# fyp_board_rev3.net
KiCad netlist of a schematic drawn in EAGLE
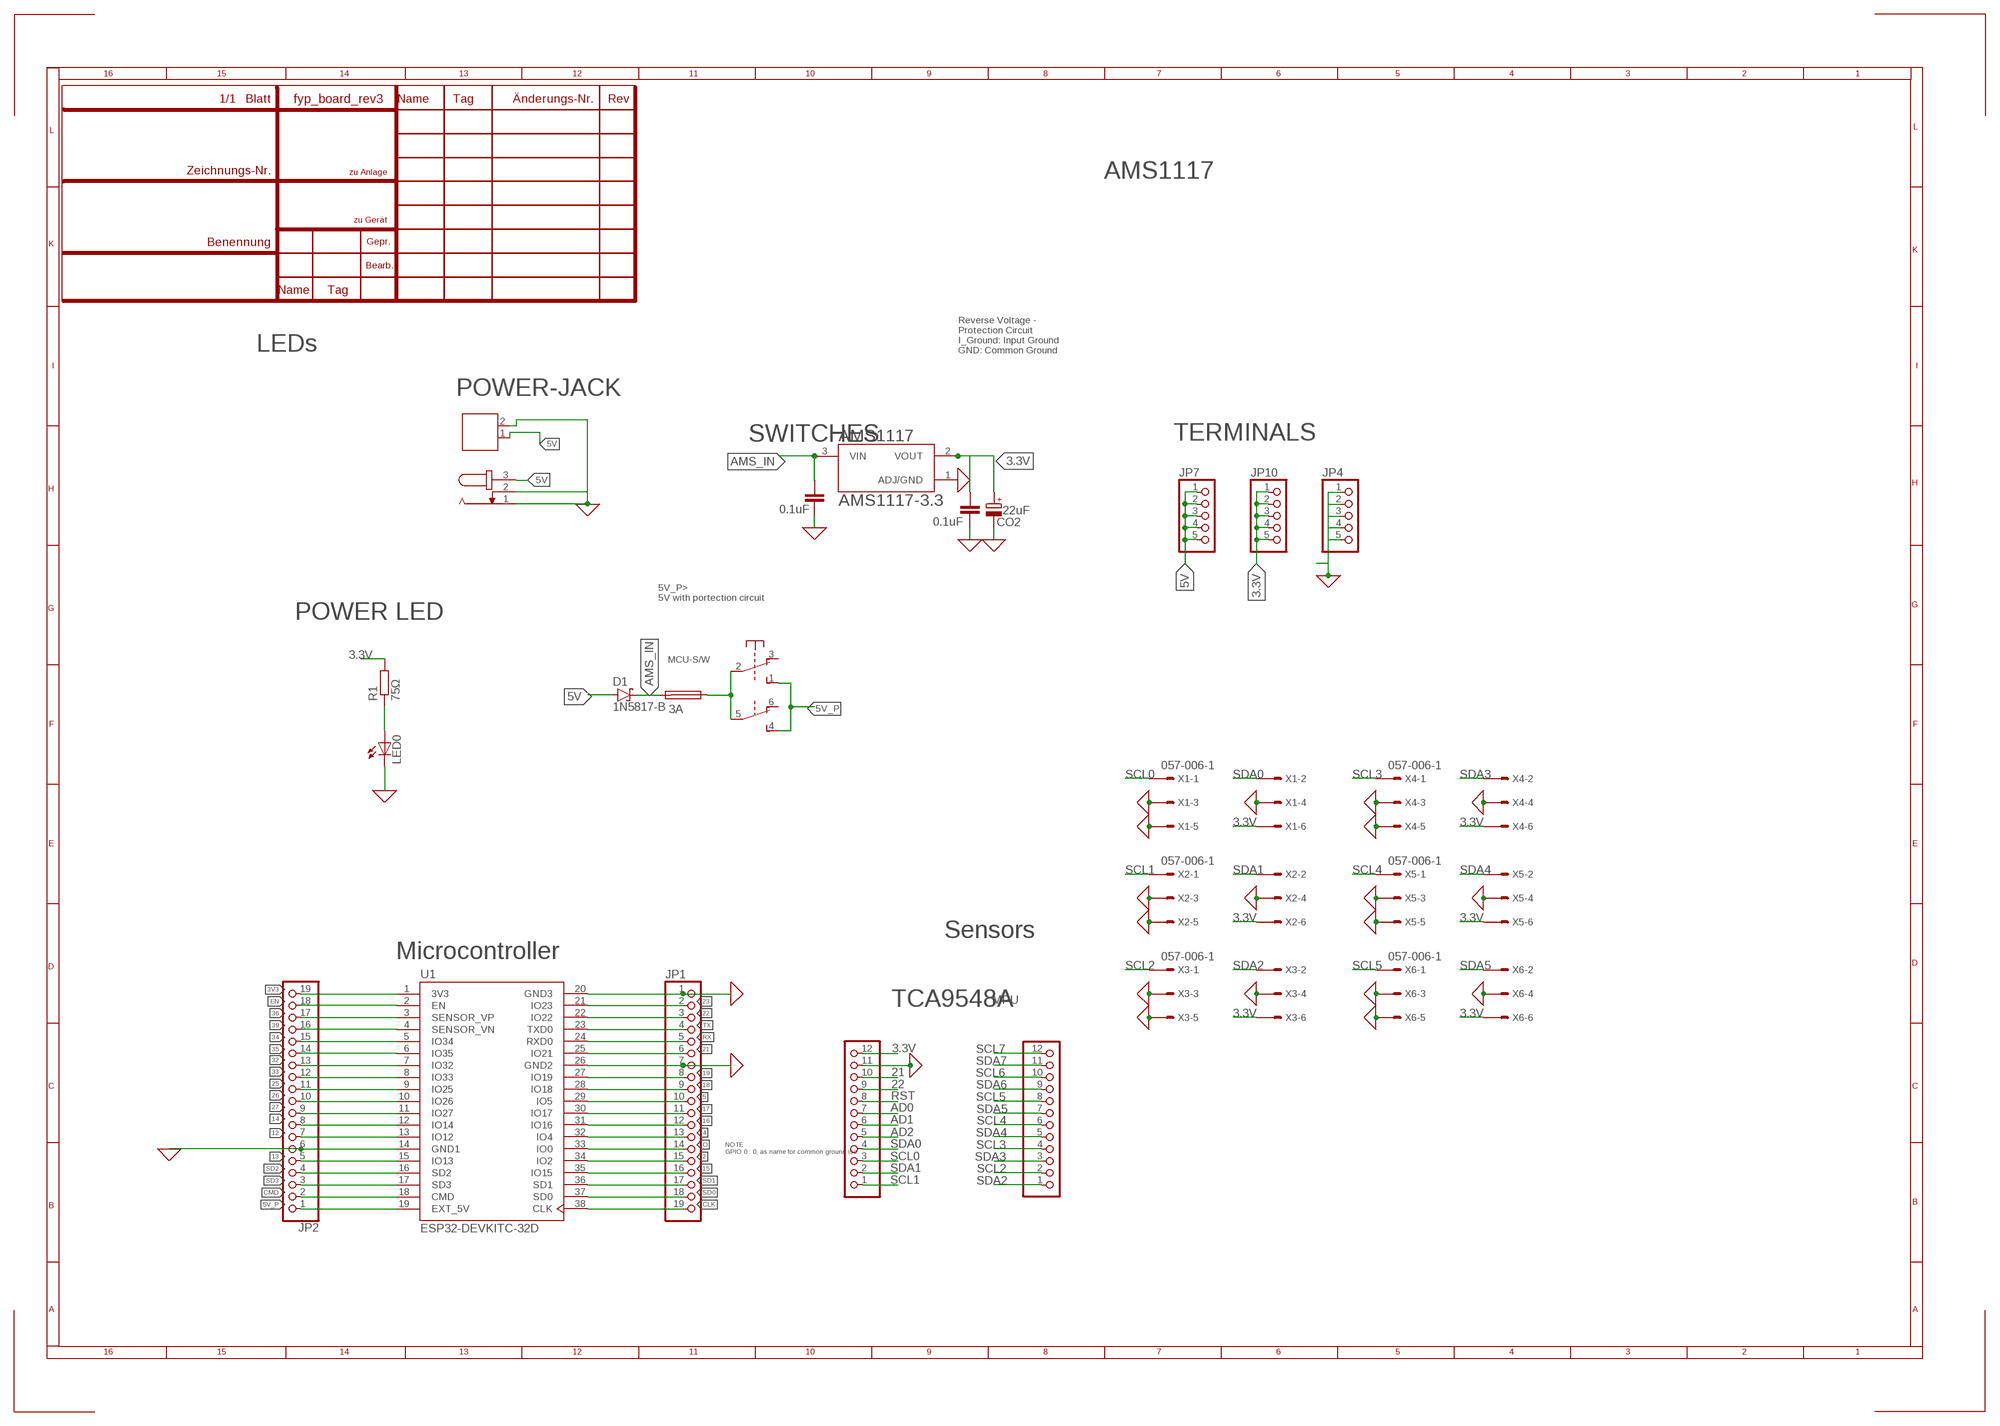
[diagram p0: schematic, sheet 1]

(export (version "E")
  (design (tool "Eeschema 10.0.6"))
  (components
    (comp (ref "12V")
      (value "691131710002")
      (footprint "eagle-import:691131710002")
      (libsource (lib "eagle-import") (part "691131710002"))
    )
    (comp (ref "AMS1117")
      (value "AMS1117-3.3")
      (footprint "eagle-import:SOT229P700X180-4N")
      (fields (field (name "MF") "Advanced Monolithic Systems"))
      (libsource (lib "eagle-import") (part "AMS1117-3.3"))
    )
    (comp (ref "CIN1")
      (value "0.1uF")
      (footprint "eagle-import:C5B2.5")
      (libsource (lib "eagle-import") (part "C5/2.5"))
    )
    (comp (ref "CO1")
      (value "0.1uF")
      (footprint "eagle-import:C5B2.5")
      (libsource (lib "eagle-import") (part "C5/2.5"))
    )
    (comp (ref "CO2")
      (value "22uF")
      (footprint "eagle-import:E2,5-6")
      (libsource (lib "eagle-import") (part "CPOL-EUE2.5-6"))
    )
    (comp (ref "D1")
      (value "1N5817-B")
      (footprint "eagle-import:DO41-7.6")
      (libsource (lib "eagle-import") (part "1N5817-B"))
    )
    (comp (ref "F2")
      (value "3A")
      (footprint "eagle-import:SH25")
      (fields (field (name "MF") "SCHURTER") (field (name "MPN") "0031.8211"))
      (libsource (lib "eagle-import") (part "SH25"))
    )
    (comp (ref "JP1")
      (value "PINHD-1X19")
      (footprint "eagle-import:1X19")
      (libsource (lib "eagle-import") (part "PINHD-1X19"))
    )
    (comp (ref "JP2")
      (value "PINHD-1X19")
      (footprint "eagle-import:1X19")
      (libsource (lib "eagle-import") (part "PINHD-1X19"))
    )
    (comp (ref "JP4")
      (value "PINHD-1X5")
      (footprint "eagle-import:1X05")
      (libsource (lib "eagle-import") (part "PINHD-1X5"))
    )
    (comp (ref "JP7")
      (value "PINHD-1X5")
      (footprint "eagle-import:1X05")
      (libsource (lib "eagle-import") (part "PINHD-1X5"))
    )
    (comp (ref "JP10")
      (value "PINHD-1X5")
      (footprint "eagle-import:1X05")
      (libsource (lib "eagle-import") (part "PINHD-1X5"))
    )
    (comp (ref "LED0")
      (value "LED3MM")
      (footprint "eagle-import:LED3MM")
      (libsource (lib "eagle-import") (part "LED3MM"))
    )
    (comp (ref "MCU-S/W")
      (value "9077-2")
      (footprint "eagle-import:9077-2")
      (libsource (lib "eagle-import") (part "9077-2"))
    )
    (comp (ref "POWER-JACK")
      (value "JACK-PLUG1")
      (footprint "eagle-import:SPC4078")
      (libsource (lib "eagle-import") (part "JACK-PLUG1"))
    )
    (comp (ref "R1")
      (value "75Ω")
      (footprint "eagle-import:0207_10")
      (libsource (lib "eagle-import") (part "R-EU_0207/10"))
    )
    (comp (ref "SV2")
      (value "PINHD-1X12")
      (footprint "eagle-import:1X12")
      (libsource (lib "eagle-import") (part "PINHD-1X12"))
    )
    (comp (ref "TCA9548")
      (value "PINHD-1X12")
      (footprint "eagle-import:1X12")
      (libsource (lib "eagle-import") (part "PINHD-1X12"))
    )
    (comp (ref "U1")
      (value "ESP32-DEVKITC-32D")
      (footprint "eagle-import:MODULE_ESP32-DEVKITC-32D")
      (fields (field (name "MF") "Espressif Systems"))
      (libsource (lib "eagle-import") (part "ESP32-DEVKITC-32D"))
    )
    (comp (ref "X1")
      (value "057-006-1")
      (footprint "eagle-import:057-006-1")
      (libsource (lib "eagle-import") (part "057-006-1"))
    )
    (comp (ref "X2")
      (value "057-006-1")
      (footprint "eagle-import:057-006-1")
      (libsource (lib "eagle-import") (part "057-006-1"))
    )
    (comp (ref "X3")
      (value "057-006-1")
      (footprint "eagle-import:057-006-1")
      (libsource (lib "eagle-import") (part "057-006-1"))
    )
    (comp (ref "X4")
      (value "057-006-1")
      (footprint "eagle-import:057-006-1")
      (libsource (lib "eagle-import") (part "057-006-1"))
    )
    (comp (ref "X5")
      (value "057-006-1")
      (footprint "eagle-import:057-006-1")
      (libsource (lib "eagle-import") (part "057-006-1"))
    )
    (comp (ref "X6")
      (value "057-006-1")
      (footprint "eagle-import:057-006-1")
      (libsource (lib "eagle-import") (part "057-006-1"))
    )
  )
  (nets
    (net (code "1") (name "/AD0") (class "Default")
      (node (ref "TCA9548") (pin "7") (pinfunction "7_7") (pintype "passive"))
    )
    (net (code "2") (name "/AD1") (class "Default")
      (node (ref "TCA9548") (pin "6") (pinfunction "6_6") (pintype "passive"))
    )
    (net (code "3") (name "/AD2") (class "Default")
      (node (ref "TCA9548") (pin "5") (pinfunction "5_5") (pintype "passive"))
    )
    (net (code "4") (name "/RST") (class "Default")
      (node (ref "TCA9548") (pin "8") (pinfunction "8_8") (pintype "passive"))
    )
    (net (code "5") (name "/SCL0") (class "Default")
      (node (ref "TCA9548") (pin "3") (pinfunction "3_3") (pintype "passive"))
      (node (ref "X1") (pin "1") (pinfunction "S_1") (pintype "passive"))
    )
    (net (code "6") (name "/SCL1") (class "Default")
      (node (ref "TCA9548") (pin "1") (pinfunction "1_1") (pintype "passive"))
      (node (ref "X2") (pin "1") (pinfunction "S_1") (pintype "passive"))
    )
    (net (code "7") (name "/SCL2") (class "Default")
      (node (ref "SV2") (pin "2") (pinfunction "2_2") (pintype "passive"))
      (node (ref "X3") (pin "1") (pinfunction "S_1") (pintype "passive"))
    )
    (net (code "8") (name "/SCL3") (class "Default")
      (node (ref "SV2") (pin "4") (pinfunction "4_4") (pintype "passive"))
      (node (ref "X4") (pin "1") (pinfunction "S_1") (pintype "passive"))
    )
    (net (code "9") (name "/SCL4") (class "Default")
      (node (ref "SV2") (pin "6") (pinfunction "6_6") (pintype "passive"))
      (node (ref "X5") (pin "1") (pinfunction "S_1") (pintype "passive"))
    )
    (net (code "10") (name "/SCL5") (class "Default")
      (node (ref "SV2") (pin "8") (pinfunction "8_8") (pintype "passive"))
      (node (ref "X6") (pin "1") (pinfunction "S_1") (pintype "passive"))
    )
    (net (code "11") (name "/SCL6") (class "Default")
      (node (ref "SV2") (pin "10") (pinfunction "10_10") (pintype "passive"))
    )
    (net (code "12") (name "/SCL7") (class "Default")
      (node (ref "SV2") (pin "12") (pinfunction "12_12") (pintype "passive"))
    )
    (net (code "13") (name "/SDA0") (class "Default")
      (node (ref "TCA9548") (pin "4") (pinfunction "4_4") (pintype "passive"))
      (node (ref "X1") (pin "2") (pinfunction "S_2") (pintype "passive"))
    )
    (net (code "14") (name "/SDA1") (class "Default")
      (node (ref "TCA9548") (pin "2") (pinfunction "2_2") (pintype "passive"))
      (node (ref "X2") (pin "2") (pinfunction "S_2") (pintype "passive"))
    )
    (net (code "15") (name "/SDA2") (class "Default")
      (node (ref "SV2") (pin "1") (pinfunction "1_1") (pintype "passive"))
      (node (ref "X3") (pin "2") (pinfunction "S_2") (pintype "passive"))
    )
    (net (code "16") (name "/SDA3") (class "Default")
      (node (ref "SV2") (pin "3") (pinfunction "3_3") (pintype "passive"))
      (node (ref "X4") (pin "2") (pinfunction "S_2") (pintype "passive"))
    )
    (net (code "17") (name "/SDA4") (class "Default")
      (node (ref "SV2") (pin "5") (pinfunction "5_5") (pintype "passive"))
      (node (ref "X5") (pin "2") (pinfunction "S_2") (pintype "passive"))
    )
    (net (code "18") (name "/SDA5") (class "Default")
      (node (ref "SV2") (pin "7") (pinfunction "7_7") (pintype "passive"))
      (node (ref "X6") (pin "2") (pinfunction "S_2") (pintype "passive"))
    )
    (net (code "19") (name "/SDA6") (class "Default")
      (node (ref "SV2") (pin "9") (pinfunction "9_9") (pintype "passive"))
    )
    (net (code "20") (name "/SDA7") (class "Default")
      (node (ref "SV2") (pin "11") (pinfunction "11_11") (pintype "passive"))
    )
    (net (code "21") (name "2") (class "Default")
      (node (ref "JP1") (pin "15") (pinfunction "15_15") (pintype "passive"))
      (node (ref "U1") (pin "34") (pinfunction "IO2_34") (pintype "bidirectional"))
    )
    (net (code "22") (name "3.3V") (class "Default")
      (node (ref "AMS1117") (pin "2") (pinfunction "VOUT_2") (pintype "output"))
      (node (ref "CO1") (pin "2") (pinfunction "2_2") (pintype "passive"))
      (node (ref "CO2") (pin "+") (pinfunction "+_+") (pintype "passive"))
      (node (ref "JP10") (pin "1") (pinfunction "1_1") (pintype "passive"))
      (node (ref "JP10") (pin "2") (pinfunction "2_2") (pintype "passive"))
      (node (ref "JP10") (pin "3") (pinfunction "3_3") (pintype "passive"))
      (node (ref "JP10") (pin "4") (pinfunction "4_4") (pintype "passive"))
      (node (ref "JP10") (pin "5") (pinfunction "5_5") (pintype "passive"))
      (node (ref "R1") (pin "2") (pinfunction "2_2") (pintype "passive"))
      (node (ref "TCA9548") (pin "12") (pinfunction "12_12") (pintype "passive"))
      (node (ref "X1") (pin "6") (pinfunction "S_6") (pintype "passive"))
      (node (ref "X2") (pin "6") (pinfunction "S_6") (pintype "passive"))
      (node (ref "X3") (pin "6") (pinfunction "S_6") (pintype "passive"))
      (node (ref "X4") (pin "6") (pinfunction "S_6") (pintype "passive"))
      (node (ref "X5") (pin "6") (pinfunction "S_6") (pintype "passive"))
      (node (ref "X6") (pin "6") (pinfunction "S_6") (pintype "passive"))
    )
    (net (code "23") (name "3V3") (class "Default")
      (node (ref "JP2") (pin "19") (pinfunction "19_19") (pintype "passive"))
      (node (ref "U1") (pin "1") (pinfunction "3V3_1") (pintype "power_in"))
    )
    (net (code "24") (name "4") (class "Default")
      (node (ref "JP1") (pin "13") (pinfunction "13_13") (pintype "passive"))
      (node (ref "U1") (pin "32") (pinfunction "IO4_32") (pintype "bidirectional"))
    )
    (net (code "25") (name "5") (class "Default")
      (node (ref "JP1") (pin "10") (pinfunction "10_10") (pintype "passive"))
      (node (ref "U1") (pin "29") (pinfunction "IO5_29") (pintype "bidirectional"))
    )
    (net (code "26") (name "5V") (class "Default")
      (node (ref "12V") (pin "1") (pinfunction "1_1") (pintype "passive"))
      (node (ref "D1") (pin "A") (pinfunction "A_A") (pintype "passive"))
      (node (ref "JP7") (pin "1") (pinfunction "1_1") (pintype "passive"))
      (node (ref "JP7") (pin "2") (pinfunction "2_2") (pintype "passive"))
      (node (ref "JP7") (pin "3") (pinfunction "3_3") (pintype "passive"))
      (node (ref "JP7") (pin "4") (pinfunction "4_4") (pintype "passive"))
      (node (ref "JP7") (pin "5") (pinfunction "5_5") (pintype "passive"))
      (node (ref "POWER-JACK") (pin "3") (pinfunction "3_3") (pintype "passive"))
    )
    (net (code "27") (name "5V_P") (class "Default")
      (node (ref "JP2") (pin "1") (pinfunction "1_1") (pintype "passive"))
      (node (ref "MCU-S/W") (pin "1") (pinfunction "S_1") (pintype "passive"))
      (node (ref "MCU-S/W") (pin "4") (pinfunction "S_4") (pintype "passive"))
      (node (ref "U1") (pin "19") (pinfunction "EXT_5V_19") (pintype "power_in"))
    )
    (net (code "28") (name "12") (class "Default")
      (node (ref "JP2") (pin "7") (pinfunction "7_7") (pintype "passive"))
      (node (ref "U1") (pin "13") (pinfunction "IO12_13") (pintype "bidirectional"))
    )
    (net (code "29") (name "13") (class "Default")
      (node (ref "JP2") (pin "5") (pinfunction "5_5") (pintype "passive"))
      (node (ref "U1") (pin "15") (pinfunction "IO13_15") (pintype "bidirectional"))
    )
    (net (code "30") (name "14") (class "Default")
      (node (ref "JP2") (pin "8") (pinfunction "8_8") (pintype "passive"))
      (node (ref "U1") (pin "12") (pinfunction "IO14_12") (pintype "bidirectional"))
    )
    (net (code "31") (name "15") (class "Default")
      (node (ref "JP1") (pin "16") (pinfunction "16_16") (pintype "passive"))
      (node (ref "U1") (pin "35") (pinfunction "IO15_35") (pintype "bidirectional"))
    )
    (net (code "32") (name "16") (class "Default")
      (node (ref "JP1") (pin "12") (pinfunction "12_12") (pintype "passive"))
      (node (ref "U1") (pin "31") (pinfunction "IO16_31") (pintype "bidirectional"))
    )
    (net (code "33") (name "17") (class "Default")
      (node (ref "JP1") (pin "11") (pinfunction "11_11") (pintype "passive"))
      (node (ref "U1") (pin "30") (pinfunction "IO17_30") (pintype "bidirectional"))
    )
    (net (code "34") (name "18") (class "Default")
      (node (ref "JP1") (pin "9") (pinfunction "9_9") (pintype "passive"))
      (node (ref "U1") (pin "28") (pinfunction "IO18_28") (pintype "bidirectional"))
    )
    (net (code "35") (name "19") (class "Default")
      (node (ref "JP1") (pin "8") (pinfunction "8_8") (pintype "passive"))
      (node (ref "U1") (pin "27") (pinfunction "IO19_27") (pintype "bidirectional"))
    )
    (net (code "36") (name "21") (class "Default")
      (node (ref "JP1") (pin "6") (pinfunction "6_6") (pintype "passive"))
      (node (ref "TCA9548") (pin "10") (pinfunction "10_10") (pintype "passive"))
      (node (ref "U1") (pin "25") (pinfunction "IO21_25") (pintype "bidirectional"))
    )
    (net (code "37") (name "22") (class "Default")
      (node (ref "JP1") (pin "3") (pinfunction "3_3") (pintype "passive"))
      (node (ref "TCA9548") (pin "9") (pinfunction "9_9") (pintype "passive"))
      (node (ref "U1") (pin "22") (pinfunction "IO22_22") (pintype "bidirectional"))
    )
    (net (code "38") (name "23") (class "Default")
      (node (ref "JP1") (pin "2") (pinfunction "2_2") (pintype "passive"))
      (node (ref "U1") (pin "21") (pinfunction "IO23_21") (pintype "bidirectional"))
    )
    (net (code "39") (name "25") (class "Default")
      (node (ref "JP2") (pin "11") (pinfunction "11_11") (pintype "passive"))
      (node (ref "U1") (pin "9") (pinfunction "IO25_9") (pintype "bidirectional"))
    )
    (net (code "40") (name "26") (class "Default")
      (node (ref "JP2") (pin "10") (pinfunction "10_10") (pintype "passive"))
      (node (ref "U1") (pin "10") (pinfunction "IO26_10") (pintype "bidirectional"))
    )
    (net (code "41") (name "27") (class "Default")
      (node (ref "JP2") (pin "9") (pinfunction "9_9") (pintype "passive"))
      (node (ref "U1") (pin "11") (pinfunction "IO27_11") (pintype "bidirectional"))
    )
    (net (code "42") (name "32") (class "Default")
      (node (ref "JP2") (pin "13") (pinfunction "13_13") (pintype "passive"))
      (node (ref "U1") (pin "7") (pinfunction "IO32_7") (pintype "bidirectional"))
    )
    (net (code "43") (name "33") (class "Default")
      (node (ref "JP2") (pin "12") (pinfunction "12_12") (pintype "passive"))
      (node (ref "U1") (pin "8") (pinfunction "IO33_8") (pintype "bidirectional"))
    )
    (net (code "44") (name "34") (class "Default")
      (node (ref "JP2") (pin "15") (pinfunction "15_15") (pintype "passive"))
      (node (ref "U1") (pin "5") (pinfunction "IO34_5") (pintype "bidirectional"))
    )
    (net (code "45") (name "35") (class "Default")
      (node (ref "JP2") (pin "14") (pinfunction "14_14") (pintype "passive"))
      (node (ref "U1") (pin "6") (pinfunction "IO35_6") (pintype "bidirectional"))
    )
    (net (code "46") (name "36") (class "Default")
      (node (ref "JP2") (pin "17") (pinfunction "17_17") (pintype "passive"))
      (node (ref "U1") (pin "3") (pinfunction "SENSOR_VP_3") (pintype "input"))
    )
    (net (code "47") (name "39") (class "Default")
      (node (ref "JP2") (pin "16") (pinfunction "16_16") (pintype "passive"))
      (node (ref "U1") (pin "4") (pinfunction "SENSOR_VN_4") (pintype "input"))
    )
    (net (code "48") (name "AMS_IN") (class "Default")
      (node (ref "AMS1117") (pin "3") (pinfunction "VIN_3") (pintype "input"))
      (node (ref "CIN1") (pin "2") (pinfunction "2_2") (pintype "passive"))
      (node (ref "D1") (pin "C") (pinfunction "C_C") (pintype "passive"))
      (node (ref "F2") (pin "2") (pinfunction "2_2") (pintype "passive"))
    )
    (net (code "49") (name "CLK") (class "Default")
      (node (ref "JP1") (pin "19") (pinfunction "19_19") (pintype "passive"))
      (node (ref "U1") (pin "38") (pinfunction "CLK_38") (pintype "input"))
    )
    (net (code "50") (name "CMD") (class "Default")
      (node (ref "JP2") (pin "2") (pinfunction "2_2") (pintype "passive"))
      (node (ref "U1") (pin "18") (pinfunction "CMD_18") (pintype "bidirectional"))
    )
    (net (code "51") (name "EN") (class "Default")
      (node (ref "JP2") (pin "18") (pinfunction "18_18") (pintype "passive"))
      (node (ref "U1") (pin "2") (pinfunction "EN_2") (pintype "input"))
    )
    (net (code "52") (name "GND") (class "Default")
      (node (ref "12V") (pin "2") (pinfunction "2_2") (pintype "passive"))
      (node (ref "AMS1117") (pin "1") (pinfunction "ADJ/GND_1") (pintype "power_in"))
      (node (ref "CIN1") (pin "1") (pinfunction "1_1") (pintype "passive"))
      (node (ref "CO1") (pin "1") (pinfunction "1_1") (pintype "passive"))
      (node (ref "CO2") (pin "-") (pinfunction "-_-") (pintype "passive"))
      (node (ref "JP1") (pin "1") (pinfunction "1_1") (pintype "passive"))
      (node (ref "JP1") (pin "7") (pinfunction "7_7") (pintype "passive"))
      (node (ref "JP2") (pin "6") (pinfunction "6_6") (pintype "passive"))
      (node (ref "JP4") (pin "1") (pinfunction "1_1") (pintype "passive"))
      (node (ref "JP4") (pin "2") (pinfunction "2_2") (pintype "passive"))
      (node (ref "JP4") (pin "3") (pinfunction "3_3") (pintype "passive"))
      (node (ref "JP4") (pin "4") (pinfunction "4_4") (pintype "passive"))
      (node (ref "JP4") (pin "5") (pinfunction "5_5") (pintype "passive"))
      (node (ref "LED0") (pin "K") (pinfunction "C_K") (pintype "passive"))
      (node (ref "POWER-JACK") (pin "1") (pinfunction "1_1") (pintype "passive"))
      (node (ref "POWER-JACK") (pin "2") (pinfunction "2_2") (pintype "passive"))
      (node (ref "TCA9548") (pin "11") (pinfunction "11_11") (pintype "passive"))
      (node (ref "U1") (pin "14") (pinfunction "GND1_14") (pintype "power_in"))
      (node (ref "U1") (pin "20") (pinfunction "GND3_20") (pintype "power_in"))
      (node (ref "U1") (pin "26") (pinfunction "GND2_26") (pintype "power_in"))
      (node (ref "X1") (pin "3") (pinfunction "S_3") (pintype "passive"))
      (node (ref "X1") (pin "4") (pinfunction "S_4") (pintype "passive"))
      (node (ref "X1") (pin "5") (pinfunction "S_5") (pintype "passive"))
      (node (ref "X2") (pin "3") (pinfunction "S_3") (pintype "passive"))
      (node (ref "X2") (pin "4") (pinfunction "S_4") (pintype "passive"))
      (node (ref "X2") (pin "5") (pinfunction "S_5") (pintype "passive"))
      (node (ref "X3") (pin "3") (pinfunction "S_3") (pintype "passive"))
      (node (ref "X3") (pin "4") (pinfunction "S_4") (pintype "passive"))
      (node (ref "X3") (pin "5") (pinfunction "S_5") (pintype "passive"))
      (node (ref "X4") (pin "3") (pinfunction "S_3") (pintype "passive"))
      (node (ref "X4") (pin "4") (pinfunction "S_4") (pintype "passive"))
      (node (ref "X4") (pin "5") (pinfunction "S_5") (pintype "passive"))
      (node (ref "X5") (pin "3") (pinfunction "S_3") (pintype "passive"))
      (node (ref "X5") (pin "4") (pinfunction "S_4") (pintype "passive"))
      (node (ref "X5") (pin "5") (pinfunction "S_5") (pintype "passive"))
      (node (ref "X6") (pin "3") (pinfunction "S_3") (pintype "passive"))
      (node (ref "X6") (pin "4") (pinfunction "S_4") (pintype "passive"))
      (node (ref "X6") (pin "5") (pinfunction "S_5") (pintype "passive"))
    )
    (net (code "53") (name "Net-(LED0-PadA)") (class "Default")
      (node (ref "LED0") (pin "A") (pinfunction "A_A") (pintype "passive"))
      (node (ref "R1") (pin "1") (pinfunction "1_1") (pintype "passive"))
    )
    (net (code "54") (name "Net-(MCU-S/WA-P)") (class "Default")
      (node (ref "F2") (pin "1") (pinfunction "1_1") (pintype "passive"))
      (node (ref "MCU-S/W") (pin "2") (pinfunction "P_2") (pintype "passive"))
      (node (ref "MCU-S/W") (pin "5") (pinfunction "P_5") (pintype "passive"))
    )
    (net (code "55") (name "O") (class "Default")
      (node (ref "JP1") (pin "14") (pinfunction "14_14") (pintype "passive"))
      (node (ref "U1") (pin "33") (pinfunction "IO0_33") (pintype "bidirectional"))
    )
    (net (code "56") (name "RX") (class "Default")
      (node (ref "JP1") (pin "5") (pinfunction "5_5") (pintype "passive"))
      (node (ref "U1") (pin "24") (pinfunction "RXD0_24") (pintype "input"))
    )
    (net (code "57") (name "SD0") (class "Default")
      (node (ref "JP1") (pin "18") (pinfunction "18_18") (pintype "passive"))
      (node (ref "U1") (pin "37") (pinfunction "SD0_37") (pintype "bidirectional"))
    )
    (net (code "58") (name "SD1") (class "Default")
      (node (ref "JP1") (pin "17") (pinfunction "17_17") (pintype "passive"))
      (node (ref "U1") (pin "36") (pinfunction "SD1_36") (pintype "bidirectional"))
    )
    (net (code "59") (name "SD2") (class "Default")
      (node (ref "JP2") (pin "4") (pinfunction "4_4") (pintype "passive"))
      (node (ref "U1") (pin "16") (pinfunction "SD2_16") (pintype "bidirectional"))
    )
    (net (code "60") (name "SD3") (class "Default")
      (node (ref "JP2") (pin "3") (pinfunction "3_3") (pintype "passive"))
      (node (ref "U1") (pin "17") (pinfunction "SD3_17") (pintype "bidirectional"))
    )
    (net (code "61") (name "TX") (class "Default")
      (node (ref "JP1") (pin "4") (pinfunction "4_4") (pintype "passive"))
      (node (ref "U1") (pin "23") (pinfunction "TXD0_23") (pintype "output"))
    )
    (net (code "62") (name "unconnected-(MCU-S/WA-O-Pad3)") (class "Default")
      (node (ref "MCU-S/W") (pin "3") (pinfunction "O_3") (pintype "passive"))
    )
    (net (code "63") (name "unconnected-(MCU-S/WB-O-Pad6)") (class "Default")
      (node (ref "MCU-S/W") (pin "6") (pinfunction "O_6") (pintype "passive"))
    )
  )
)
